# Solar_Charger.net
KiCad netlist of a schematic drawn in EAGLE
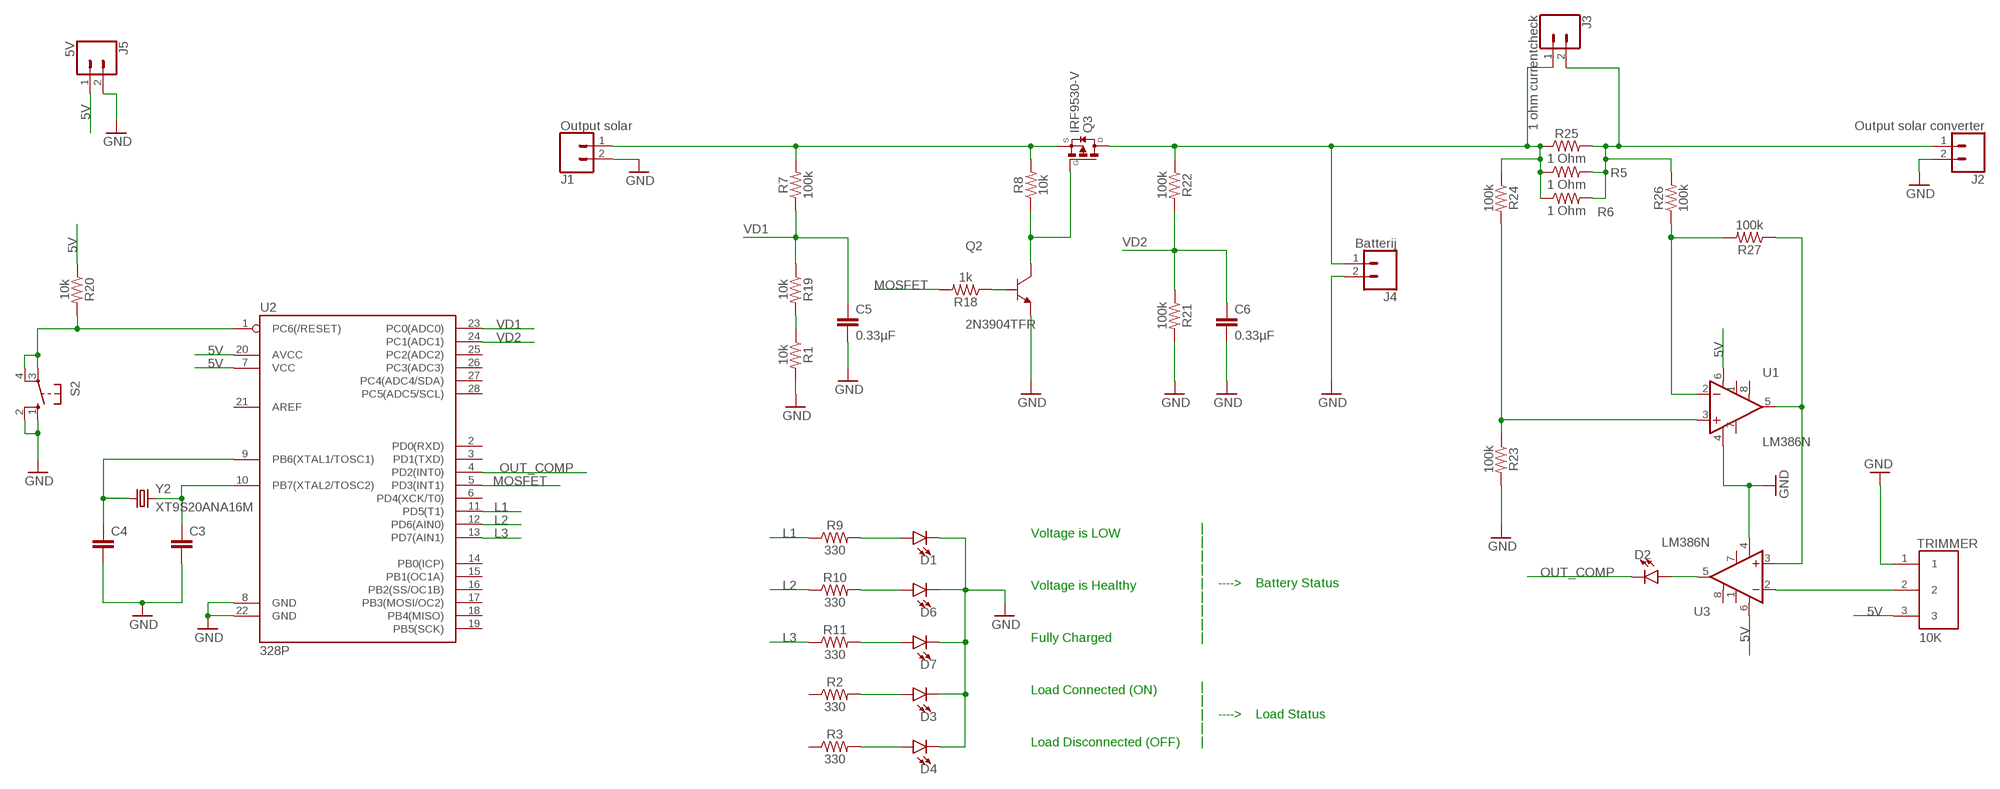
[diagram p0: schematic, sheet 1]

(export (version "E")
  (design (tool "Eeschema 10.0.6"))
  (components
    (comp (ref "C3")
      (value "C2.5/5")
      (footprint "eagle-import:C2.5-5")
      (libsource (lib "eagle-import") (part "C2.5/5"))
    )
    (comp (ref "C4")
      (value "C2.5/5")
      (footprint "eagle-import:C2.5-5")
      (libsource (lib "eagle-import") (part "C2.5/5"))
    )
    (comp (ref "C5")
      (value "0.33µF")
      (footprint "eagle-import:C2.5-5")
      (libsource (lib "eagle-import") (part "C2.5/5"))
    )
    (comp (ref "C6")
      (value "0.33µF")
      (footprint "eagle-import:C2.5-5")
      (libsource (lib "eagle-import") (part "C2.5/5"))
    )
    (comp (ref "D1")
      (value "LED-3MM-NO_SILK")
      (footprint "eagle-import:LED_3MM-NS")
      (libsource (lib "eagle-import") (part "LED-3MM-NO_SILK"))
    )
    (comp (ref "D2")
      (value "LED-3MM-NO_SILK")
      (footprint "eagle-import:LED_3MM-NS")
      (libsource (lib "eagle-import") (part "LED-3MM-NO_SILK"))
    )
    (comp (ref "D3")
      (value "LED-3MM-NO_SILK")
      (footprint "eagle-import:LED_3MM-NS")
      (libsource (lib "eagle-import") (part "LED-3MM-NO_SILK"))
    )
    (comp (ref "D4")
      (value "LED-3MM-NO_SILK")
      (footprint "eagle-import:LED_3MM-NS")
      (libsource (lib "eagle-import") (part "LED-3MM-NO_SILK"))
    )
    (comp (ref "D6")
      (value "LED-3MM-NO_SILK")
      (footprint "eagle-import:LED_3MM-NS")
      (libsource (lib "eagle-import") (part "LED-3MM-NO_SILK"))
    )
    (comp (ref "D7")
      (value "LED-3MM-NO_SILK")
      (footprint "eagle-import:LED_3MM-NS")
      (libsource (lib "eagle-import") (part "LED-3MM-NO_SILK"))
    )
    (comp (ref "J1")
      (value "Output solar")
      (footprint "eagle-import:1X02")
      (libsource (lib "eagle-import") (part "CONN_02"))
    )
    (comp (ref "J2")
      (value "Output solar converter")
      (footprint "eagle-import:1X02")
      (libsource (lib "eagle-import") (part "CONN_02"))
    )
    (comp (ref "J3")
      (value "1 ohm currentcheck")
      (footprint "eagle-import:1X02")
      (libsource (lib "eagle-import") (part "CONN_02"))
    )
    (comp (ref "J4")
      (value "Batterij")
      (footprint "eagle-import:1X02")
      (libsource (lib "eagle-import") (part "CONN_02"))
    )
    (comp (ref "J5")
      (value "5V")
      (footprint "eagle-import:1X02")
      (libsource (lib "eagle-import") (part "CONN_02"))
    )
    (comp (ref "Q2")
      (value "2N3904TFR")
      (footprint "eagle-import:TO92254P520H877-3")
      (fields (field (name "MF") "ON Semiconductor"))
      (libsource (lib "eagle-import") (part "2N3904TFR"))
    )
    (comp (ref "Q3")
      (value "IRF9530-V")
      (footprint "eagle-import:TO220V")
      (fields (field (name "MF") "Vishay") (field (name "MP") "IRF9530"))
      (libsource (lib "eagle-import") (part "IRF9530-V"))
    )
    (comp (ref "R1")
      (value "10k")
      (footprint "eagle-import:AXIAL-0.3")
      (libsource (lib "eagle-import") (part "1MOHM-HORIZ-1/4W-5%"))
    )
    (comp (ref "R2")
      (value "330")
      (footprint "eagle-import:AXIAL-0.3")
      (libsource (lib "eagle-import") (part "1KOHM-HORIZ-1/4W-1%"))
    )
    (comp (ref "R3")
      (value "330")
      (footprint "eagle-import:AXIAL-0.3")
      (libsource (lib "eagle-import") (part "1KOHM-HORIZ-1/4W-1%"))
    )
    (comp (ref "R5")
      (value "1 Ohm")
      (footprint "eagle-import:AXIAL-0.3")
      (libsource (lib "eagle-import") (part "1MOHM-HORIZ-1/4W-5%"))
    )
    (comp (ref "R6")
      (value "1 Ohm")
      (footprint "eagle-import:AXIAL-0.3")
      (libsource (lib "eagle-import") (part "1MOHM-HORIZ-1/4W-5%"))
    )
    (comp (ref "R7")
      (value "100k")
      (footprint "eagle-import:AXIAL-0.3")
      (libsource (lib "eagle-import") (part "1MOHM-HORIZ-1/4W-5%"))
    )
    (comp (ref "R8")
      (value "10k")
      (footprint "eagle-import:AXIAL-0.3")
      (libsource (lib "eagle-import") (part "1MOHM-HORIZ-1/4W-5%"))
    )
    (comp (ref "R9")
      (value "330")
      (footprint "eagle-import:AXIAL-0.3")
      (libsource (lib "eagle-import") (part "1KOHM-HORIZ-1/4W-1%"))
    )
    (comp (ref "R10")
      (value "330")
      (footprint "eagle-import:AXIAL-0.3")
      (libsource (lib "eagle-import") (part "1KOHM-HORIZ-1/4W-1%"))
    )
    (comp (ref "R11")
      (value "330")
      (footprint "eagle-import:AXIAL-0.3")
      (libsource (lib "eagle-import") (part "1KOHM-HORIZ-1/4W-1%"))
    )
    (comp (ref "R18")
      (value "1k")
      (footprint "eagle-import:AXIAL-0.3")
      (libsource (lib "eagle-import") (part "1MOHM-HORIZ-1/4W-5%"))
    )
    (comp (ref "R19")
      (value "10k")
      (footprint "eagle-import:AXIAL-0.3")
      (libsource (lib "eagle-import") (part "1MOHM-HORIZ-1/4W-5%"))
    )
    (comp (ref "R20")
      (value "10k")
      (footprint "eagle-import:AXIAL-0.3")
      (libsource (lib "eagle-import") (part "1MOHM-HORIZ-1/4W-5%"))
    )
    (comp (ref "R21")
      (value "100k")
      (footprint "eagle-import:AXIAL-0.3")
      (libsource (lib "eagle-import") (part "1MOHM-HORIZ-1/4W-5%"))
    )
    (comp (ref "R22")
      (value "100k")
      (footprint "eagle-import:AXIAL-0.3")
      (libsource (lib "eagle-import") (part "1MOHM-HORIZ-1/4W-5%"))
    )
    (comp (ref "R23")
      (value "100k")
      (footprint "eagle-import:AXIAL-0.3")
      (libsource (lib "eagle-import") (part "1MOHM-HORIZ-1/4W-5%"))
    )
    (comp (ref "R24")
      (value "100k")
      (footprint "eagle-import:AXIAL-0.3")
      (libsource (lib "eagle-import") (part "1MOHM-HORIZ-1/4W-5%"))
    )
    (comp (ref "R25")
      (value "1 Ohm")
      (footprint "eagle-import:AXIAL-0.3")
      (libsource (lib "eagle-import") (part "1MOHM-HORIZ-1/4W-5%"))
    )
    (comp (ref "R26")
      (value "100k")
      (footprint "eagle-import:AXIAL-0.3")
      (libsource (lib "eagle-import") (part "1MOHM-HORIZ-1/4W-5%"))
    )
    (comp (ref "R27")
      (value "100k")
      (footprint "eagle-import:AXIAL-0.3")
      (libsource (lib "eagle-import") (part "1MOHM-HORIZ-1/4W-5%"))
    )
    (comp (ref "S2")
      (value "10-XX")
      (footprint "eagle-import:B3F-10XX")
      (fields (field (name "MPN") "B3F-1000"))
      (libsource (lib "eagle-import") (part "10-XX"))
    )
    (comp (ref "TRIMMER")
      (value "10K")
      (footprint "eagle-import:TRIM_404806347006")
      (fields
        (field (name "COMMENT") "1623831-6")
        (field (name "MF") "TE Connectivity")
        (field (name "MP") "404806347006")
      )
      (libsource (lib "eagle-import") (part "404806347006"))
    )
    (comp (ref "U1")
      (value "LM386N")
      (footprint "eagle-import:DIP08")
      (libsource (lib "eagle-import") (part "LM386"))
    )
    (comp (ref "U2")
      (value "328P")
      (footprint "eagle-import:DIP28")
      (libsource (lib "eagle-import") (part "ATMEGA328P_PDIP"))
    )
    (comp (ref "U3")
      (value "LM386N")
      (footprint "eagle-import:DIP08")
      (libsource (lib "eagle-import") (part "LM386"))
    )
    (comp (ref "Y2")
      (value "XT9S20ANA16M")
      (footprint "eagle-import:XTAL_XT9S20ANA16M")
      (fields (field (name "MF") "Vishay"))
      (libsource (lib "eagle-import") (part "XT9S20ANA16M"))
    )
  )
  (nets
    (net (code "1") (name "/5V") (class "Default")
      (node (ref "J5") (pin "1") (pinfunction "1_1") (pintype "passive"))
      (node (ref "R20") (pin "P$1") (pinfunction "1_P$1") (pintype "passive"))
      (node (ref "TRIMMER") (pin "3") (pinfunction "3_3") (pintype "passive"))
      (node (ref "U1") (pin "6") (pinfunction "V+_6") (pintype "power_in"))
      (node (ref "U2") (pin "20") (pinfunction "AVCC_20") (pintype "bidirectional"))
      (node (ref "U2") (pin "7") (pinfunction "VCC_7") (pintype "bidirectional"))
      (node (ref "U3") (pin "6") (pinfunction "V+_6") (pintype "power_in"))
    )
    (net (code "2") (name "/L1") (class "Default")
      (node (ref "R9") (pin "P$1") (pinfunction "1_P$1") (pintype "passive"))
      (node (ref "U2") (pin "11") (pinfunction "PD5(T1)_11") (pintype "bidirectional"))
    )
    (net (code "3") (name "/L2") (class "Default")
      (node (ref "R10") (pin "P$1") (pinfunction "1_P$1") (pintype "passive"))
      (node (ref "U2") (pin "12") (pinfunction "PD6(AIN0)_12") (pintype "bidirectional"))
    )
    (net (code "4") (name "/L3") (class "Default")
      (node (ref "R11") (pin "P$1") (pinfunction "1_P$1") (pintype "passive"))
      (node (ref "U2") (pin "13") (pinfunction "PD7(AIN1)_13") (pintype "bidirectional"))
    )
    (net (code "5") (name "/MOSFET") (class "Default")
      (node (ref "R18") (pin "P$2") (pinfunction "2_P$2") (pintype "passive"))
      (node (ref "U2") (pin "5") (pinfunction "PD3(INT1)_5") (pintype "bidirectional"))
    )
    (net (code "6") (name "/OUT_COMP") (class "Default")
      (node (ref "D2") (pin "K") (pinfunction "C_K") (pintype "passive"))
      (node (ref "U2") (pin "4") (pinfunction "PD2(INT0)_4") (pintype "bidirectional"))
    )
    (net (code "7") (name "/VD1") (class "Default")
      (node (ref "C5") (pin "1") (pinfunction "1_1") (pintype "passive"))
      (node (ref "R19") (pin "P$1") (pinfunction "1_P$1") (pintype "passive"))
      (node (ref "R7") (pin "P$1") (pinfunction "1_P$1") (pintype "passive"))
      (node (ref "U2") (pin "23") (pinfunction "PC0(ADC0)_23") (pintype "bidirectional"))
    )
    (net (code "8") (name "/VD2") (class "Default")
      (node (ref "C6") (pin "1") (pinfunction "1_1") (pintype "passive"))
      (node (ref "R21") (pin "P$1") (pinfunction "1_P$1") (pintype "passive"))
      (node (ref "R22") (pin "P$2") (pinfunction "2_P$2") (pintype "passive"))
      (node (ref "U2") (pin "24") (pinfunction "PC1(ADC1)_24") (pintype "bidirectional"))
    )
    (net (code "9") (name "GND") (class "Default")
      (node (ref "C3") (pin "2") (pinfunction "2_2") (pintype "passive"))
      (node (ref "C4") (pin "2") (pinfunction "2_2") (pintype "passive"))
      (node (ref "C5") (pin "2") (pinfunction "2_2") (pintype "passive"))
      (node (ref "C6") (pin "2") (pinfunction "2_2") (pintype "passive"))
      (node (ref "D1") (pin "K") (pinfunction "C_K") (pintype "passive"))
      (node (ref "D3") (pin "K") (pinfunction "C_K") (pintype "passive"))
      (node (ref "D4") (pin "K") (pinfunction "C_K") (pintype "passive"))
      (node (ref "D6") (pin "K") (pinfunction "C_K") (pintype "passive"))
      (node (ref "D7") (pin "K") (pinfunction "C_K") (pintype "passive"))
      (node (ref "J1") (pin "2") (pinfunction "2_2") (pintype "passive"))
      (node (ref "J2") (pin "2") (pinfunction "2_2") (pintype "passive"))
      (node (ref "J4") (pin "2") (pinfunction "2_2") (pintype "passive"))
      (node (ref "J5") (pin "2") (pinfunction "2_2") (pintype "passive"))
      (node (ref "Q2") (pin "1") (pinfunction "E_1") (pintype "passive"))
      (node (ref "R1") (pin "P$2") (pinfunction "2_P$2") (pintype "passive"))
      (node (ref "R21") (pin "P$2") (pinfunction "2_P$2") (pintype "passive"))
      (node (ref "R23") (pin "P$2") (pinfunction "2_P$2") (pintype "passive"))
      (node (ref "S2") (pin "1") (pinfunction "S_1") (pintype "passive"))
      (node (ref "S2") (pin "2") (pinfunction "S1_2") (pintype "passive"))
      (node (ref "TRIMMER") (pin "1") (pinfunction "1_1") (pintype "passive"))
      (node (ref "U1") (pin "4") (pinfunction "V-_4") (pintype "power_in"))
      (node (ref "U2") (pin "22") (pinfunction "GND_22") (pintype "bidirectional"))
      (node (ref "U2") (pin "8") (pinfunction "GND_8") (pintype "bidirectional"))
      (node (ref "U3") (pin "4") (pinfunction "V-_4") (pintype "power_in"))
    )
    (net (code "10") (name "Net-(Q2-B)") (class "Default")
      (node (ref "Q2") (pin "2") (pinfunction "B_2") (pintype "passive"))
      (node (ref "R18") (pin "P$1") (pinfunction "1_P$1") (pintype "passive"))
    )
    (net (code "11") (name "Net-(Q2-C)") (class "Default")
      (node (ref "Q2") (pin "3") (pinfunction "C_3") (pintype "passive"))
      (node (ref "Q3") (pin "1") (pinfunction "G_1") (pintype "passive"))
      (node (ref "R8") (pin "P$1") (pinfunction "1_P$1") (pintype "passive"))
    )
    (net (code "12") (name "Net-(Q3-D)") (class "Default")
      (node (ref "J3") (pin "1") (pinfunction "1_1") (pintype "passive"))
      (node (ref "J4") (pin "1") (pinfunction "1_1") (pintype "passive"))
      (node (ref "Q3") (pin "2") (pinfunction "D_2") (pintype "passive"))
      (node (ref "R22") (pin "P$1") (pinfunction "1_P$1") (pintype "passive"))
      (node (ref "R24") (pin "P$1") (pinfunction "1_P$1") (pintype "passive"))
      (node (ref "R25") (pin "P$1") (pinfunction "1_P$1") (pintype "passive"))
      (node (ref "R5") (pin "P$1") (pinfunction "1_P$1") (pintype "passive"))
      (node (ref "R6") (pin "P$1") (pinfunction "1_P$1") (pintype "passive"))
    )
    (net (code "13") (name "Net-(Q3-S)") (class "Default")
      (node (ref "J1") (pin "1") (pinfunction "1_1") (pintype "passive"))
      (node (ref "Q3") (pin "3") (pinfunction "S_3") (pintype "passive"))
      (node (ref "R7") (pin "P$2") (pinfunction "2_P$2") (pintype "passive"))
      (node (ref "R8") (pin "P$2") (pinfunction "2_P$2") (pintype "passive"))
    )
    (net (code "14") (name "Net-(R1-1)") (class "Default")
      (node (ref "R1") (pin "P$1") (pinfunction "1_P$1") (pintype "passive"))
      (node (ref "R19") (pin "P$2") (pinfunction "2_P$2") (pintype "passive"))
    )
    (net (code "15") (name "Net-(R2-2)") (class "Default")
      (node (ref "D3") (pin "A") (pinfunction "A_A") (pintype "passive"))
      (node (ref "R2") (pin "P$2") (pinfunction "2_P$2") (pintype "passive"))
    )
    (net (code "16") (name "Net-(R3-2)") (class "Default")
      (node (ref "D4") (pin "A") (pinfunction "A_A") (pintype "passive"))
      (node (ref "R3") (pin "P$2") (pinfunction "2_P$2") (pintype "passive"))
    )
    (net (code "17") (name "Net-(R9-2)") (class "Default")
      (node (ref "D1") (pin "A") (pinfunction "A_A") (pintype "passive"))
      (node (ref "R9") (pin "P$2") (pinfunction "2_P$2") (pintype "passive"))
    )
    (net (code "18") (name "Net-(R10-2)") (class "Default")
      (node (ref "D6") (pin "A") (pinfunction "A_A") (pintype "passive"))
      (node (ref "R10") (pin "P$2") (pinfunction "2_P$2") (pintype "passive"))
    )
    (net (code "19") (name "Net-(R11-2)") (class "Default")
      (node (ref "D7") (pin "A") (pinfunction "A_A") (pintype "passive"))
      (node (ref "R11") (pin "P$2") (pinfunction "2_P$2") (pintype "passive"))
    )
    (net (code "20") (name "Net-(R20-2)") (class "Default")
      (node (ref "R20") (pin "P$2") (pinfunction "2_P$2") (pintype "passive"))
      (node (ref "S2") (pin "3") (pinfunction "P_3") (pintype "passive"))
      (node (ref "S2") (pin "4") (pinfunction "P1_4") (pintype "passive"))
      (node (ref "U2") (pin "1") (pinfunction "PC6(/RESET)_1") (pintype "bidirectional"))
    )
    (net (code "21") (name "Net-(R23-1)") (class "Default")
      (node (ref "R23") (pin "P$1") (pinfunction "1_P$1") (pintype "passive"))
      (node (ref "R24") (pin "P$2") (pinfunction "2_P$2") (pintype "passive"))
      (node (ref "U1") (pin "3") (pinfunction "+IN_3") (pintype "input"))
    )
    (net (code "22") (name "Net-(R25-2)") (class "Default")
      (node (ref "J2") (pin "1") (pinfunction "1_1") (pintype "passive"))
      (node (ref "J3") (pin "2") (pinfunction "2_2") (pintype "passive"))
      (node (ref "R25") (pin "P$2") (pinfunction "2_P$2") (pintype "passive"))
      (node (ref "R26") (pin "P$2") (pinfunction "2_P$2") (pintype "passive"))
      (node (ref "R5") (pin "P$2") (pinfunction "2_P$2") (pintype "passive"))
      (node (ref "R6") (pin "P$2") (pinfunction "2_P$2") (pintype "passive"))
    )
    (net (code "23") (name "Net-(R26-1)") (class "Default")
      (node (ref "R26") (pin "P$1") (pinfunction "1_P$1") (pintype "passive"))
      (node (ref "R27") (pin "P$2") (pinfunction "2_P$2") (pintype "passive"))
      (node (ref "U1") (pin "2") (pinfunction "-IN_2") (pintype "input"))
    )
    (net (code "24") (name "Net-(R27-1)") (class "Default")
      (node (ref "R27") (pin "P$1") (pinfunction "1_P$1") (pintype "passive"))
      (node (ref "U1") (pin "5") (pinfunction "OUT_5") (pintype "output"))
      (node (ref "U3") (pin "3") (pinfunction "+IN_3") (pintype "input"))
    )
    (net (code "25") (name "Net-(U2-PB6(XTAL1{slash}TOSC1))") (class "Default")
      (node (ref "C4") (pin "1") (pinfunction "1_1") (pintype "passive"))
      (node (ref "U2") (pin "9") (pinfunction "PB6(XTAL1/TOSC1)_9") (pintype "bidirectional"))
      (node (ref "Y2") (pin "1") (pinfunction "1_1") (pintype "passive"))
    )
    (net (code "26") (name "Net-(U2-PB7(XTAL2{slash}TOSC2))") (class "Default")
      (node (ref "C3") (pin "1") (pinfunction "1_1") (pintype "passive"))
      (node (ref "U2") (pin "10") (pinfunction "PB7(XTAL2/TOSC2)_10") (pintype "bidirectional"))
      (node (ref "Y2") (pin "2") (pinfunction "2_2") (pintype "passive"))
    )
    (net (code "27") (name "Net-(U3--IN)") (class "Default")
      (node (ref "TRIMMER") (pin "2") (pinfunction "2_2") (pintype "passive"))
      (node (ref "U3") (pin "2") (pinfunction "-IN_2") (pintype "input"))
    )
    (net (code "28") (name "Net-(U3-OUT)") (class "Default")
      (node (ref "D2") (pin "A") (pinfunction "A_A") (pintype "passive"))
      (node (ref "U3") (pin "5") (pinfunction "OUT_5") (pintype "output"))
    )
    (net (code "29") (name "unconnected-(R2-1-PadP$1)") (class "Default")
      (node (ref "R2") (pin "P$1") (pinfunction "1_P$1") (pintype "passive"))
    )
    (net (code "30") (name "unconnected-(R3-1-PadP$1)") (class "Default")
      (node (ref "R3") (pin "P$1") (pinfunction "1_P$1") (pintype "passive"))
    )
    (net (code "31") (name "unconnected-(U1-BP-Pad7)") (class "Default")
      (node (ref "U1") (pin "7") (pinfunction "BP_7") (pintype "bidirectional"))
    )
    (net (code "32") (name "unconnected-(U1-GAIN-Pad1)") (class "Default")
      (node (ref "U1") (pin "1") (pinfunction "GAIN_1") (pintype "bidirectional"))
    )
    (net (code "33") (name "unconnected-(U1-GAIN-Pad8)") (class "Default")
      (node (ref "U1") (pin "8") (pinfunction "GAIN_8") (pintype "bidirectional"))
    )
    (net (code "34") (name "unconnected-(U2-AREF-Pad21)") (class "Default")
      (node (ref "U2") (pin "21") (pinfunction "AREF_21") (pintype "bidirectional"))
    )
    (net (code "35") (name "unconnected-(U2-PB0(ICP)-Pad14)") (class "Default")
      (node (ref "U2") (pin "14") (pinfunction "PB0(ICP)_14") (pintype "bidirectional"))
    )
    (net (code "36") (name "unconnected-(U2-PB1(OC1A)-Pad15)") (class "Default")
      (node (ref "U2") (pin "15") (pinfunction "PB1(OC1A)_15") (pintype "bidirectional"))
    )
    (net (code "37") (name "unconnected-(U2-PB2(SS{slash}OC1B)-Pad16)") (class "Default")
      (node (ref "U2") (pin "16") (pinfunction "PB2(SS/OC1B)_16") (pintype "bidirectional"))
    )
    (net (code "38") (name "unconnected-(U2-PB3(MOSI{slash}OC2)-Pad17)") (class "Default")
      (node (ref "U2") (pin "17") (pinfunction "PB3(MOSI/OC2)_17") (pintype "bidirectional"))
    )
    (net (code "39") (name "unconnected-(U2-PB4(MISO)-Pad18)") (class "Default")
      (node (ref "U2") (pin "18") (pinfunction "PB4(MISO)_18") (pintype "bidirectional"))
    )
    (net (code "40") (name "unconnected-(U2-PB5(SCK)-Pad19)") (class "Default")
      (node (ref "U2") (pin "19") (pinfunction "PB5(SCK)_19") (pintype "bidirectional"))
    )
    (net (code "41") (name "unconnected-(U2-PC2(ADC2)-Pad25)") (class "Default")
      (node (ref "U2") (pin "25") (pinfunction "PC2(ADC2)_25") (pintype "bidirectional"))
    )
    (net (code "42") (name "unconnected-(U2-PC3(ADC3)-Pad26)") (class "Default")
      (node (ref "U2") (pin "26") (pinfunction "PC3(ADC3)_26") (pintype "bidirectional"))
    )
    (net (code "43") (name "unconnected-(U2-PC4(ADC4{slash}SDA)-Pad27)") (class "Default")
      (node (ref "U2") (pin "27") (pinfunction "PC4(ADC4/SDA)_27") (pintype "bidirectional"))
    )
    (net (code "44") (name "unconnected-(U2-PC5(ADC5{slash}SCL)-Pad28)") (class "Default")
      (node (ref "U2") (pin "28") (pinfunction "PC5(ADC5/SCL)_28") (pintype "bidirectional"))
    )
    (net (code "45") (name "unconnected-(U2-PD0(RXD)-Pad2)") (class "Default")
      (node (ref "U2") (pin "2") (pinfunction "PD0(RXD)_2") (pintype "bidirectional"))
    )
    (net (code "46") (name "unconnected-(U2-PD1(TXD)-Pad3)") (class "Default")
      (node (ref "U2") (pin "3") (pinfunction "PD1(TXD)_3") (pintype "bidirectional"))
    )
    (net (code "47") (name "unconnected-(U2-PD4(XCK{slash}T0)-Pad6)") (class "Default")
      (node (ref "U2") (pin "6") (pinfunction "PD4(XCK/T0)_6") (pintype "bidirectional"))
    )
    (net (code "48") (name "unconnected-(U3-BP-Pad7)") (class "Default")
      (node (ref "U3") (pin "7") (pinfunction "BP_7") (pintype "bidirectional"))
    )
    (net (code "49") (name "unconnected-(U3-GAIN-Pad1)") (class "Default")
      (node (ref "U3") (pin "1") (pinfunction "GAIN_1") (pintype "bidirectional"))
    )
    (net (code "50") (name "unconnected-(U3-GAIN-Pad8)") (class "Default")
      (node (ref "U3") (pin "8") (pinfunction "GAIN_8") (pintype "bidirectional"))
    )
  )
)
